# Camera_Gantry.net
KiCad netlist of a schematic drawn in EAGLE
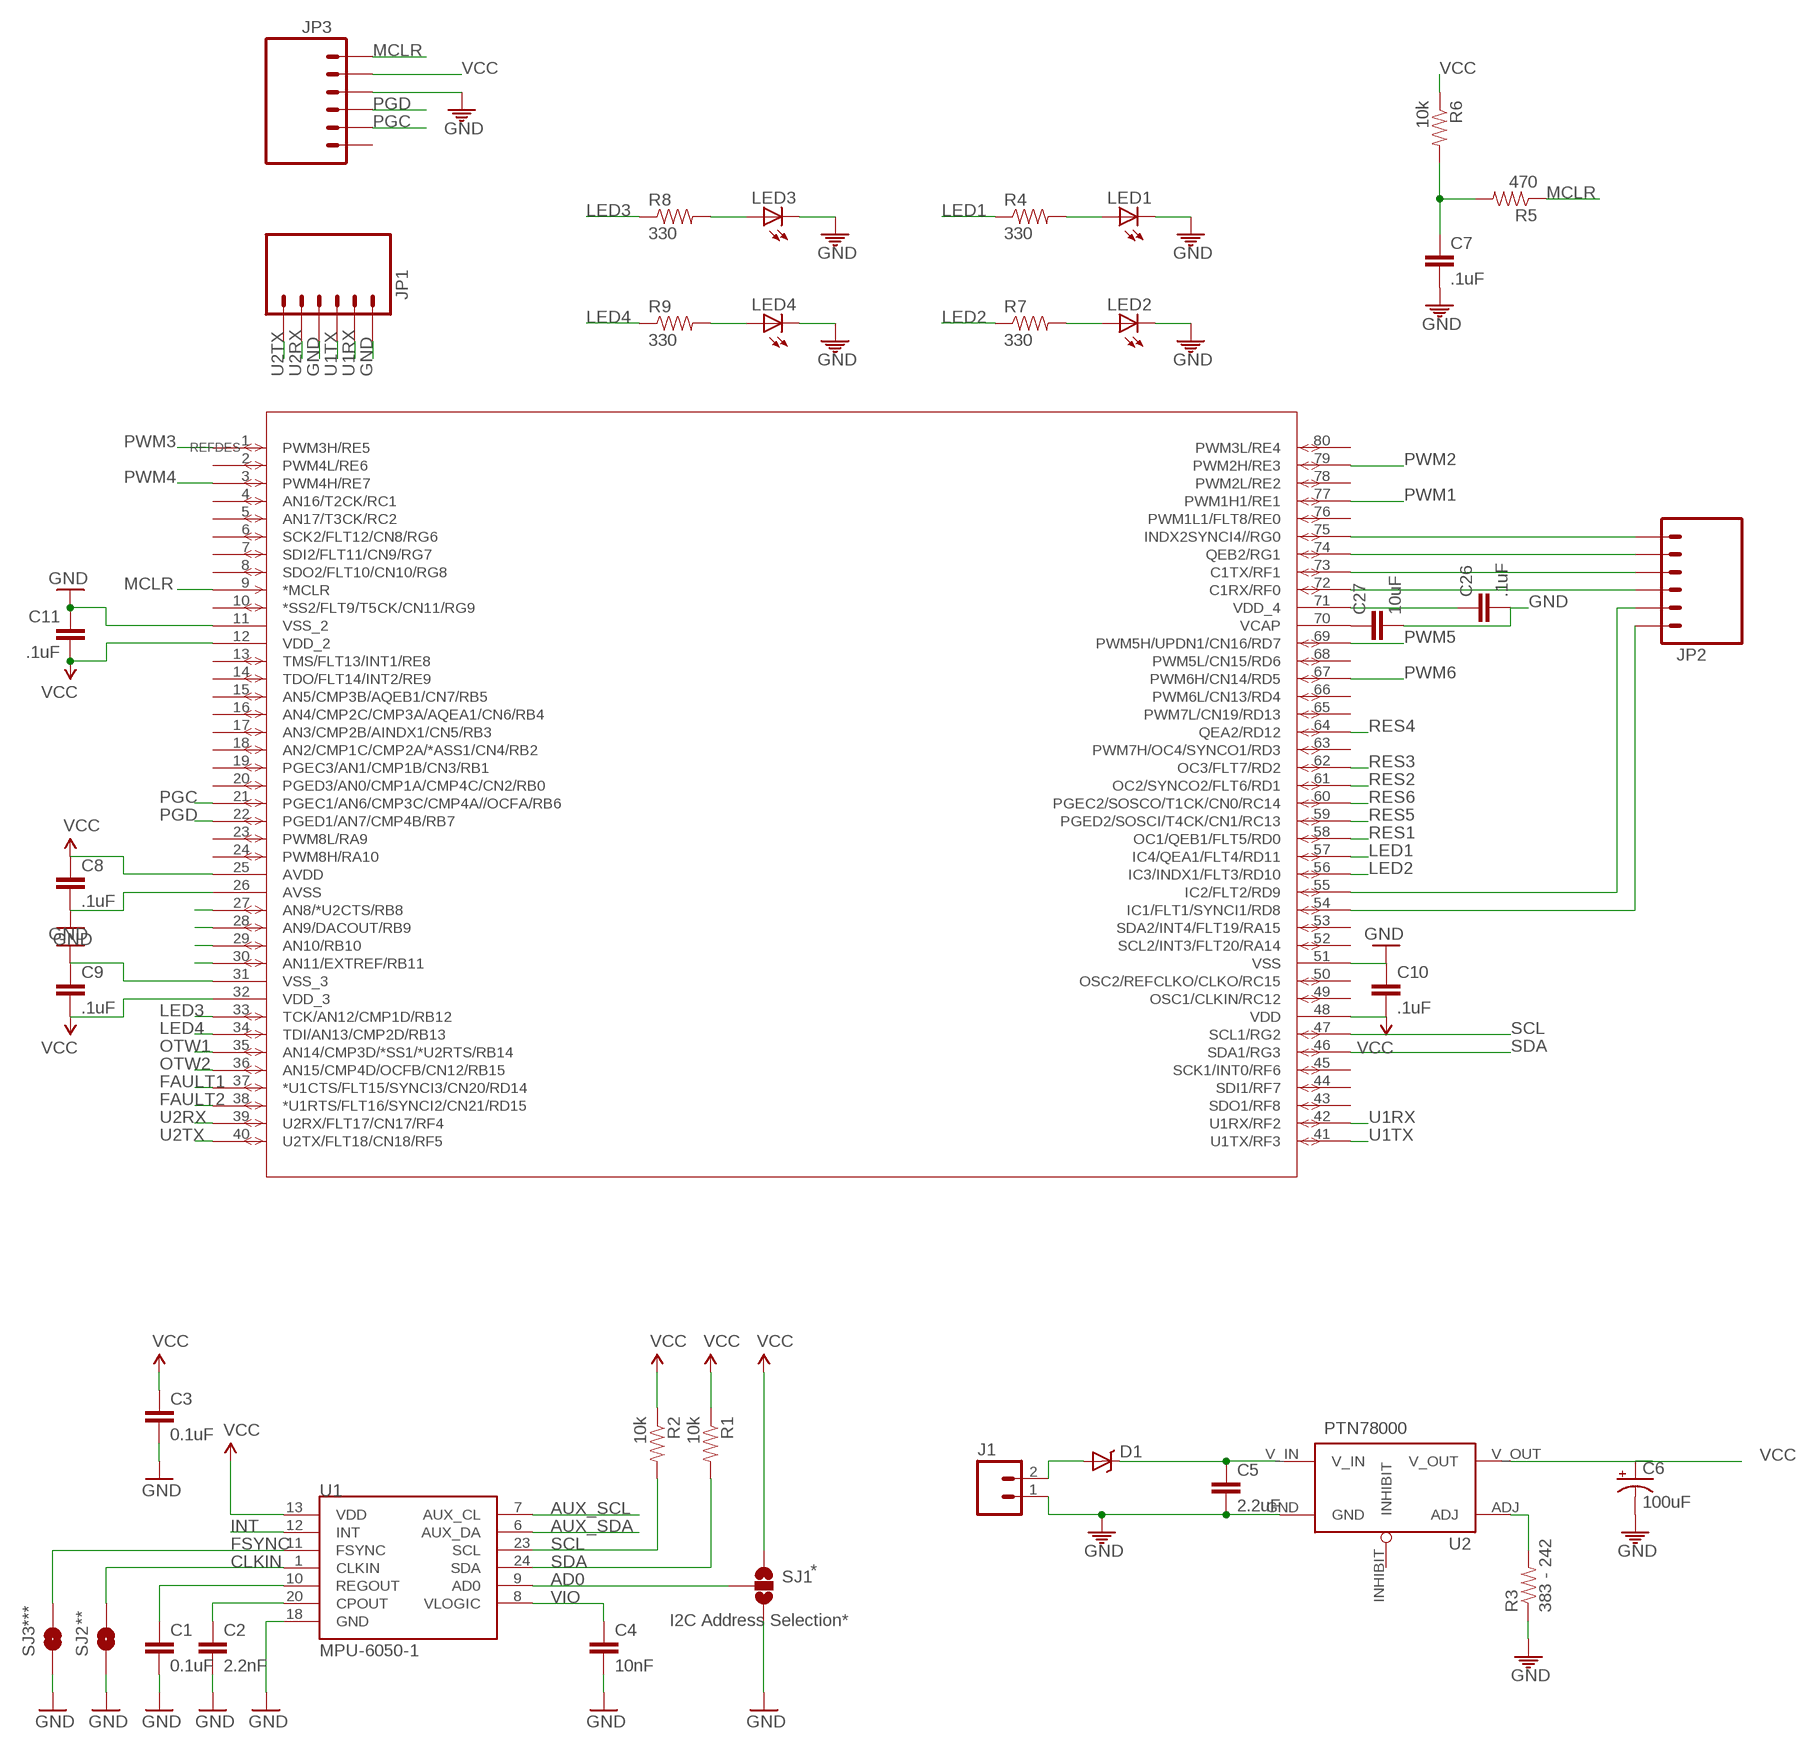
[diagram p0: schematic, sheet 1, part 1 of 2]
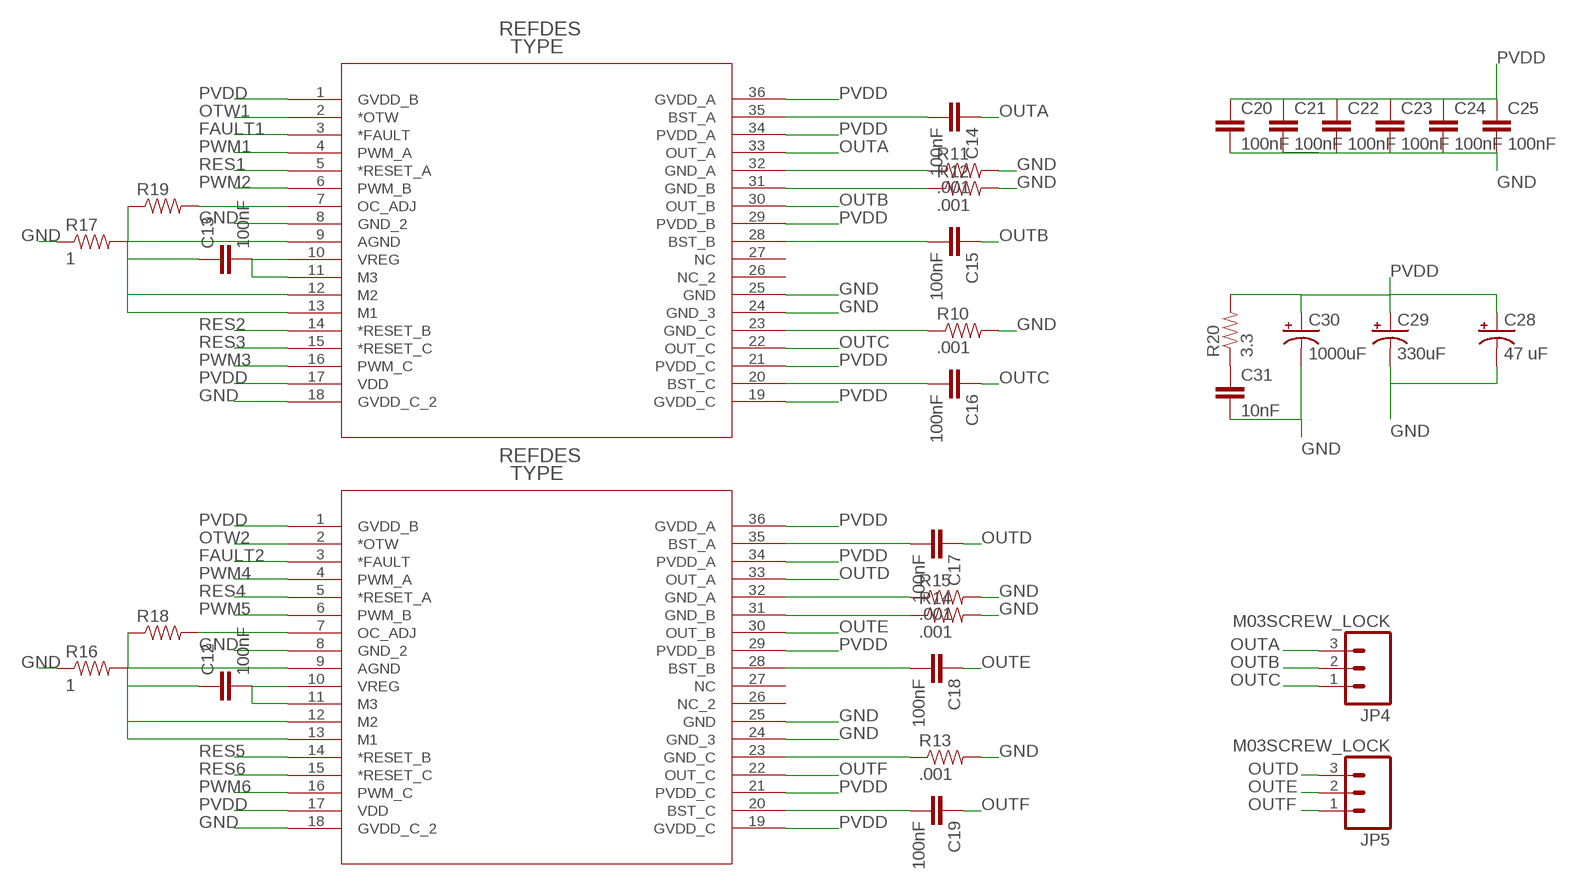
[diagram p1: schematic, sheet 1, part 2 of 2]

(export (version "E")
  (design (tool "Eeschema 10.0.6"))
  (components
    (comp (ref "C1")
      (value "0.1uF")
      (footprint "eagle-import:1206")
      (libsource (lib "eagle-import") (part "CAP1206"))
    )
    (comp (ref "C2")
      (value "2.2nF")
      (footprint "eagle-import:1206")
      (libsource (lib "eagle-import") (part "CAP1206"))
    )
    (comp (ref "C3")
      (value "0.1uF")
      (footprint "eagle-import:1206")
      (libsource (lib "eagle-import") (part "CAP1206"))
    )
    (comp (ref "C4")
      (value "10nF")
      (footprint "eagle-import:1206")
      (libsource (lib "eagle-import") (part "CAP1206"))
    )
    (comp (ref "C5")
      (value "2.2uF")
      (footprint "eagle-import:1206")
      (libsource (lib "eagle-import") (part "CMPE118lib_CAP1206"))
    )
    (comp (ref "C6")
      (value "100uF")
      (footprint "eagle-import:CPOL-RADIAL-100UF-25V")
      (libsource (lib "eagle-import") (part "CAP_POLPTH1"))
    )
    (comp (ref "C7")
      (value ".1uF")
      (footprint "eagle-import:1206")
      (libsource (lib "eagle-import") (part "CMPE118lib_CAP1206"))
    )
    (comp (ref "C8")
      (value ".1uF")
      (footprint "eagle-import:1206")
      (libsource (lib "eagle-import") (part "CAP1206"))
    )
    (comp (ref "C9")
      (value ".1uF")
      (footprint "eagle-import:1206")
      (libsource (lib "eagle-import") (part "CAP1206"))
    )
    (comp (ref "C10")
      (value ".1uF")
      (footprint "eagle-import:1206")
      (libsource (lib "eagle-import") (part "CAP1206"))
    )
    (comp (ref "C11")
      (value ".1uF")
      (footprint "eagle-import:1206")
      (libsource (lib "eagle-import") (part "CAP1206"))
    )
    (comp (ref "C12")
      (value "100nF")
      (footprint "eagle-import:1206")
      (libsource (lib "eagle-import") (part "CAP1206"))
    )
    (comp (ref "C13")
      (value "100nF")
      (footprint "eagle-import:1206")
      (libsource (lib "eagle-import") (part "CAP1206"))
    )
    (comp (ref "C14")
      (value "100nF")
      (footprint "eagle-import:1206")
      (libsource (lib "eagle-import") (part "CAP1206"))
    )
    (comp (ref "C15")
      (value "100nF")
      (footprint "eagle-import:1206")
      (libsource (lib "eagle-import") (part "CAP1206"))
    )
    (comp (ref "C16")
      (value "100nF")
      (footprint "eagle-import:1206")
      (libsource (lib "eagle-import") (part "CAP1206"))
    )
    (comp (ref "C17")
      (value "100nF")
      (footprint "eagle-import:1206")
      (libsource (lib "eagle-import") (part "CAP1206"))
    )
    (comp (ref "C18")
      (value "100nF")
      (footprint "eagle-import:1206")
      (libsource (lib "eagle-import") (part "CAP1206"))
    )
    (comp (ref "C19")
      (value "100nF")
      (footprint "eagle-import:1206")
      (libsource (lib "eagle-import") (part "CAP1206"))
    )
    (comp (ref "C20")
      (value "100nF")
      (footprint "eagle-import:1206")
      (libsource (lib "eagle-import") (part "CAP1206"))
    )
    (comp (ref "C21")
      (value "100nF")
      (footprint "eagle-import:1206")
      (libsource (lib "eagle-import") (part "CAP1206"))
    )
    (comp (ref "C22")
      (value "100nF")
      (footprint "eagle-import:1206")
      (libsource (lib "eagle-import") (part "CAP1206"))
    )
    (comp (ref "C23")
      (value "100nF")
      (footprint "eagle-import:1206")
      (libsource (lib "eagle-import") (part "CAP1206"))
    )
    (comp (ref "C24")
      (value "100nF")
      (footprint "eagle-import:1206")
      (libsource (lib "eagle-import") (part "CAP1206"))
    )
    (comp (ref "C25")
      (value "100nF")
      (footprint "eagle-import:1206")
      (libsource (lib "eagle-import") (part "CAP1206"))
    )
    (comp (ref "C26")
      (value ".1uF")
      (footprint "eagle-import:1206")
      (libsource (lib "eagle-import") (part "CAP1206"))
    )
    (comp (ref "C27")
      (value "10uF")
      (footprint "eagle-import:1206")
      (libsource (lib "eagle-import") (part "CAP1206"))
    )
    (comp (ref "C28")
      (value "47 uF")
      (footprint "eagle-import:CPOL-RADIAL-10UF-25V")
      (libsource (lib "eagle-import") (part "CAP_POLPTH2"))
    )
    (comp (ref "C29")
      (value "330uF")
      (footprint "eagle-import:CPOL-RADIAL-100UF-25V")
      (libsource (lib "eagle-import") (part "CAP_POLPTH1"))
    )
    (comp (ref "C30")
      (value "1000uF")
      (footprint "eagle-import:CPOL-RADIAL-1000UF-25V")
      (libsource (lib "eagle-import") (part "CAP_POLPTH4"))
    )
    (comp (ref "C31")
      (value "10nF")
      (footprint "eagle-import:1206")
      (libsource (lib "eagle-import") (part "CAP1206"))
    )
    (comp (ref "D1")
      (value "DIODE-SCHOTTKY240A")
      (footprint "eagle-import:SMA-DIODE-B240A")
      (libsource (lib "eagle-import") (part "DIODE-SCHOTTKY240A"))
    )
    (comp (ref "J1")
      (value "M025MM")
      (footprint "eagle-import:SCREWTERMINAL-5MM-2")
      (libsource (lib "eagle-import") (part "M025MM"))
    )
    (comp (ref "JP1")
      (value "M06SIP")
      (footprint "eagle-import:1X06")
      (libsource (lib "eagle-import") (part "M06SIP"))
    )
    (comp (ref "JP2")
      (value "M06SIP")
      (footprint "eagle-import:1X06")
      (libsource (lib "eagle-import") (part "M06SIP"))
    )
    (comp (ref "JP3")
      (value "M06LOCK")
      (footprint "eagle-import:1X06_LOCK")
      (libsource (lib "eagle-import") (part "CMPE118lib_M06LOCK"))
    )
    (comp (ref "JP4")
      (value "M03SCREW_LOCK")
      (footprint "eagle-import:SCREWTERMINAL-3.5MM-3_LOCK.007S")
      (libsource (lib "eagle-import") (part "M03SCREW_LOCK"))
    )
    (comp (ref "JP5")
      (value "M03SCREW_LOCK")
      (footprint "eagle-import:SCREWTERMINAL-3.5MM-3_LOCK.007S")
      (libsource (lib "eagle-import") (part "M03SCREW_LOCK"))
    )
    (comp (ref "LED1")
      (value "LED1206")
      (footprint "eagle-import:LED-1206")
      (fields (field (name "COLOR") "red"))
      (libsource (lib "eagle-import") (part "LED1206"))
    )
    (comp (ref "LED2")
      (value "LED1206")
      (footprint "eagle-import:LED-1206")
      (fields (field (name "COLOR") "red"))
      (libsource (lib "eagle-import") (part "LED1206"))
    )
    (comp (ref "LED3")
      (value "LED1206")
      (footprint "eagle-import:LED-1206")
      (fields (field (name "COLOR") "red"))
      (libsource (lib "eagle-import") (part "LED1206"))
    )
    (comp (ref "LED4")
      (value "LED1206")
      (footprint "eagle-import:LED-1206")
      (fields (field (name "COLOR") "red"))
      (libsource (lib "eagle-import") (part "LED1206"))
    )
    (comp (ref "R1")
      (value "10k")
      (footprint "eagle-import:0805")
      (libsource (lib "eagle-import") (part "CMPE118lib_RESISTOR0805-RES"))
    )
    (comp (ref "R2")
      (value "10k")
      (footprint "eagle-import:0805")
      (libsource (lib "eagle-import") (part "CMPE118lib_RESISTOR0805-RES"))
    )
    (comp (ref "R3")
      (value "383 - 242")
      (footprint "eagle-import:0805")
      (libsource (lib "eagle-import") (part "CMPE118lib_RESISTOR0805-RES"))
    )
    (comp (ref "R4")
      (value "330")
      (footprint "eagle-import:0805")
      (libsource (lib "eagle-import") (part "CMPE118lib_RESISTOR0805-RES"))
    )
    (comp (ref "R5")
      (value "470")
      (footprint "eagle-import:0805")
      (libsource (lib "eagle-import") (part "CMPE118lib_RESISTOR0805-RES"))
    )
    (comp (ref "R6")
      (value "10k")
      (footprint "eagle-import:0805")
      (libsource (lib "eagle-import") (part "CMPE118lib_RESISTOR0805-RES"))
    )
    (comp (ref "R7")
      (value "330")
      (footprint "eagle-import:0805")
      (libsource (lib "eagle-import") (part "CMPE118lib_RESISTOR0805-RES"))
    )
    (comp (ref "R8")
      (value "330")
      (footprint "eagle-import:0805")
      (libsource (lib "eagle-import") (part "CMPE118lib_RESISTOR0805-RES"))
    )
    (comp (ref "R9")
      (value "330")
      (footprint "eagle-import:0805")
      (libsource (lib "eagle-import") (part "CMPE118lib_RESISTOR0805-RES"))
    )
    (comp (ref "R10")
      (value ".001")
      (footprint "eagle-import:R2512")
      (libsource (lib "eagle-import") (part "RESISTOR2512"))
    )
    (comp (ref "R11")
      (value ".001")
      (footprint "eagle-import:R2512")
      (libsource (lib "eagle-import") (part "RESISTOR2512"))
    )
    (comp (ref "R12")
      (value ".001")
      (footprint "eagle-import:R2512")
      (libsource (lib "eagle-import") (part "RESISTOR2512"))
    )
    (comp (ref "R13")
      (value ".001")
      (footprint "eagle-import:R2512")
      (libsource (lib "eagle-import") (part "RESISTOR2512"))
    )
    (comp (ref "R14")
      (value ".001")
      (footprint "eagle-import:R2512")
      (libsource (lib "eagle-import") (part "RESISTOR2512"))
    )
    (comp (ref "R15")
      (value ".001")
      (footprint "eagle-import:R2512")
      (libsource (lib "eagle-import") (part "RESISTOR2512"))
    )
    (comp (ref "R16")
      (value "1")
      (footprint "eagle-import:0805")
      (libsource (lib "eagle-import") (part "RESISTOR0805-RES"))
    )
    (comp (ref "R17")
      (value "1")
      (footprint "eagle-import:0805")
      (libsource (lib "eagle-import") (part "RESISTOR0805-RES"))
    )
    (comp (ref "R18")
      (value "RESISTOR0805-RES")
      (footprint "eagle-import:0805")
      (libsource (lib "eagle-import") (part "RESISTOR0805-RES"))
    )
    (comp (ref "R19")
      (value "RESISTOR0805-RES")
      (footprint "eagle-import:0805")
      (libsource (lib "eagle-import") (part "RESISTOR0805-RES"))
    )
    (comp (ref "R20")
      (value "3.3")
      (footprint "eagle-import:0805")
      (libsource (lib "eagle-import") (part "RESISTOR0805-RES"))
    )
    (comp (ref "SJ1")
      (value "SOLDERJUMPER_2WAYPASTE2&3")
      (footprint "eagle-import:SJ_3_PASTE2&3")
      (libsource (lib "eagle-import") (part "SOLDERJUMPER_2WAYPASTE2&3"))
    )
    (comp (ref "SJ2")
      (value "SOLDERJUMPERTRACE")
      (footprint "eagle-import:SJ_2S-TRACE")
      (libsource (lib "eagle-import") (part "SOLDERJUMPERTRACE"))
    )
    (comp (ref "SJ3")
      (value "SOLDERJUMPERTRACE")
      (footprint "eagle-import:SJ_2S-TRACE")
      (libsource (lib "eagle-import") (part "SOLDERJUMPERTRACE"))
    )
    (comp (ref "U$1")
      (value "DSPIC33FJ64GS608")
      (footprint "eagle-import:TQFP80_12X12MC")
      (libsource (lib "eagle-import") (part "DSPIC33FJ64GS608"))
    )
    (comp (ref "U1")
      (value "MPU-6050-1")
      (footprint "eagle-import:QFN-24-4MM2")
      (libsource (lib "eagle-import") (part "MPU-6050-1"))
    )
    (comp (ref "U2")
      (value "PTN78000")
      (footprint "eagle-import:PTN78000")
      (libsource (lib "eagle-import") (part "PTN78000THROUGH-HOLE"))
    )
    (comp (ref "U3")
      (value "DRV8332_DKD_36")
      (footprint "eagle-import:DKD36")
      (libsource (lib "eagle-import") (part "DRV8332_DKD_36"))
    )
    (comp (ref "U4")
      (value "DRV8332_DKD_36")
      (footprint "eagle-import:DKD36")
      (libsource (lib "eagle-import") (part "DRV8332_DKD_36"))
    )
  )
  (nets
    (net (code "1") (name "/AD0") (class "Default")
      (node (ref "SJ1") (pin "2") (pinfunction "2_2") (pintype "passive"))
      (node (ref "U1") (pin "9") (pinfunction "AD0_9") (pintype "bidirectional"))
    )
    (net (code "2") (name "/AUX_SCL") (class "Default")
      (node (ref "U1") (pin "7") (pinfunction "AUX_CL_7") (pintype "bidirectional"))
    )
    (net (code "3") (name "/AUX_SDA") (class "Default")
      (node (ref "U1") (pin "6") (pinfunction "AUX_DA_6") (pintype "bidirectional"))
    )
    (net (code "4") (name "/CLKIN") (class "Default")
      (node (ref "SJ2") (pin "2") (pinfunction "2_2") (pintype "passive"))
      (node (ref "U1") (pin "1") (pinfunction "CLKIN_1") (pintype "bidirectional"))
    )
    (net (code "5") (name "/FAULT1") (class "Default")
      (node (ref "U$1") (pin "37") (pinfunction "*U1CTS/FLT15/SYNCI3/CN20/RD14_37") (pintype "passive"))
      (node (ref "U3") (pin "3") (pinfunction "*FAULT_3") (pintype "passive"))
    )
    (net (code "6") (name "/FAULT2") (class "Default")
      (node (ref "U$1") (pin "38") (pinfunction "*U1RTS/FLT16/SYNCI2/CN21/RD15_38") (pintype "passive"))
      (node (ref "U4") (pin "3") (pinfunction "*FAULT_3") (pintype "passive"))
    )
    (net (code "7") (name "/FSYNC") (class "Default")
      (node (ref "SJ3") (pin "2") (pinfunction "2_2") (pintype "passive"))
      (node (ref "U1") (pin "11") (pinfunction "FSYNC_11") (pintype "bidirectional"))
    )
    (net (code "8") (name "/INT") (class "Default")
      (node (ref "U1") (pin "12") (pinfunction "INT_12") (pintype "bidirectional"))
    )
    (net (code "9") (name "/LED1") (class "Default")
      (node (ref "R4") (pin "1") (pinfunction "1_1") (pintype "passive"))
      (node (ref "U$1") (pin "57") (pinfunction "IC4/QEA1/FLT4/RD11_57") (pintype "passive"))
    )
    (net (code "10") (name "/LED2") (class "Default")
      (node (ref "R7") (pin "1") (pinfunction "1_1") (pintype "passive"))
      (node (ref "U$1") (pin "56") (pinfunction "IC3/INDX1/FLT3/RD10_56") (pintype "passive"))
    )
    (net (code "11") (name "/LED3") (class "Default")
      (node (ref "R8") (pin "1") (pinfunction "1_1") (pintype "passive"))
      (node (ref "U$1") (pin "33") (pinfunction "TCK/AN12/CMP1D/RB12_33") (pintype "passive"))
    )
    (net (code "12") (name "/LED4") (class "Default")
      (node (ref "R9") (pin "1") (pinfunction "1_1") (pintype "passive"))
      (node (ref "U$1") (pin "34") (pinfunction "TDI/AN13/CMP2D/RB13_34") (pintype "passive"))
    )
    (net (code "13") (name "/MCLR") (class "Default")
      (node (ref "JP3") (pin "1") (pinfunction "1_1") (pintype "passive"))
      (node (ref "R5") (pin "1") (pinfunction "1_1") (pintype "passive"))
      (node (ref "U$1") (pin "9") (pinfunction "*MCLR_9") (pintype "passive"))
    )
    (net (code "14") (name "/OTW1") (class "Default")
      (node (ref "U$1") (pin "35") (pinfunction "AN14/CMP3D/*SS1/*U2RTS/RB14_35") (pintype "passive"))
      (node (ref "U3") (pin "2") (pinfunction "*OTW_2") (pintype "passive"))
    )
    (net (code "15") (name "/OTW2") (class "Default")
      (node (ref "U$1") (pin "36") (pinfunction "AN15/CMP4D/OCFB/CN12/RB15_36") (pintype "passive"))
      (node (ref "U4") (pin "2") (pinfunction "*OTW_2") (pintype "passive"))
    )
    (net (code "16") (name "/OUTA") (class "Default")
      (node (ref "C14") (pin "1") (pinfunction "1_1") (pintype "passive"))
      (node (ref "JP4") (pin "3") (pinfunction "3_3") (pintype "passive"))
      (node (ref "U3") (pin "33") (pinfunction "OUT_A_33") (pintype "passive"))
    )
    (net (code "17") (name "/OUTB") (class "Default")
      (node (ref "C15") (pin "1") (pinfunction "1_1") (pintype "passive"))
      (node (ref "JP4") (pin "2") (pinfunction "2_2") (pintype "passive"))
      (node (ref "U3") (pin "30") (pinfunction "OUT_B_30") (pintype "passive"))
    )
    (net (code "18") (name "/OUTC") (class "Default")
      (node (ref "C16") (pin "1") (pinfunction "1_1") (pintype "passive"))
      (node (ref "JP4") (pin "1") (pinfunction "1_1") (pintype "passive"))
      (node (ref "U3") (pin "22") (pinfunction "OUT_C_22") (pintype "passive"))
    )
    (net (code "19") (name "/OUTD") (class "Default")
      (node (ref "C17") (pin "1") (pinfunction "1_1") (pintype "passive"))
      (node (ref "JP5") (pin "3") (pinfunction "3_3") (pintype "passive"))
      (node (ref "U4") (pin "33") (pinfunction "OUT_A_33") (pintype "passive"))
    )
    (net (code "20") (name "/OUTE") (class "Default")
      (node (ref "C18") (pin "1") (pinfunction "1_1") (pintype "passive"))
      (node (ref "JP5") (pin "2") (pinfunction "2_2") (pintype "passive"))
      (node (ref "U4") (pin "30") (pinfunction "OUT_B_30") (pintype "passive"))
    )
    (net (code "21") (name "/OUTF") (class "Default")
      (node (ref "C19") (pin "1") (pinfunction "1_1") (pintype "passive"))
      (node (ref "JP5") (pin "1") (pinfunction "1_1") (pintype "passive"))
      (node (ref "U4") (pin "22") (pinfunction "OUT_C_22") (pintype "passive"))
    )
    (net (code "22") (name "/PGC") (class "Default")
      (node (ref "JP3") (pin "5") (pinfunction "5_5") (pintype "passive"))
      (node (ref "U$1") (pin "21") (pinfunction "PGEC1/AN6/CMP3C/CMP4A//OCFA/RB6_21") (pintype "passive"))
    )
    (net (code "23") (name "/PGD") (class "Default")
      (node (ref "JP3") (pin "4") (pinfunction "4_4") (pintype "passive"))
      (node (ref "U$1") (pin "22") (pinfunction "PGED1/AN7/CMP4B/RB7_22") (pintype "passive"))
    )
    (net (code "24") (name "/PVDD") (class "Default")
      (node (ref "C20") (pin "1") (pinfunction "1_1") (pintype "passive"))
      (node (ref "C21") (pin "1") (pinfunction "1_1") (pintype "passive"))
      (node (ref "C22") (pin "1") (pinfunction "1_1") (pintype "passive"))
      (node (ref "C23") (pin "1") (pinfunction "1_1") (pintype "passive"))
      (node (ref "C24") (pin "1") (pinfunction "1_1") (pintype "passive"))
      (node (ref "C25") (pin "1") (pinfunction "1_1") (pintype "passive"))
      (node (ref "C28") (pin "1") (pinfunction "+_1") (pintype "passive"))
      (node (ref "C29") (pin "1") (pinfunction "+_1") (pintype "passive"))
      (node (ref "C30") (pin "1") (pinfunction "+_1") (pintype "passive"))
      (node (ref "C5") (pin "1") (pinfunction "1_1") (pintype "passive"))
      (node (ref "D1") (pin "C") (pinfunction "C_C") (pintype "passive"))
      (node (ref "R20") (pin "2") (pinfunction "2_2") (pintype "passive"))
      (node (ref "U2") (pin "V_IN") (pinfunction "V_IN_V_IN") (pintype "power_in"))
      (node (ref "U3") (pin "1") (pinfunction "GVDD_B_1") (pintype "passive"))
      (node (ref "U3") (pin "17") (pinfunction "VDD_17") (pintype "passive"))
      (node (ref "U3") (pin "19") (pinfunction "GVDD_C_19") (pintype "passive"))
      (node (ref "U3") (pin "21") (pinfunction "PVDD_C_21") (pintype "passive"))
      (node (ref "U3") (pin "29") (pinfunction "PVDD_B_29") (pintype "passive"))
      (node (ref "U3") (pin "34") (pinfunction "PVDD_A_34") (pintype "passive"))
      (node (ref "U3") (pin "36") (pinfunction "GVDD_A_36") (pintype "passive"))
      (node (ref "U4") (pin "1") (pinfunction "GVDD_B_1") (pintype "passive"))
      (node (ref "U4") (pin "17") (pinfunction "VDD_17") (pintype "passive"))
      (node (ref "U4") (pin "19") (pinfunction "GVDD_C_19") (pintype "passive"))
      (node (ref "U4") (pin "21") (pinfunction "PVDD_C_21") (pintype "passive"))
      (node (ref "U4") (pin "29") (pinfunction "PVDD_B_29") (pintype "passive"))
      (node (ref "U4") (pin "34") (pinfunction "PVDD_A_34") (pintype "passive"))
      (node (ref "U4") (pin "36") (pinfunction "GVDD_A_36") (pintype "passive"))
    )
    (net (code "25") (name "/PWM1") (class "Default")
      (node (ref "U$1") (pin "77") (pinfunction "PWM1H1/RE1_77") (pintype "passive"))
      (node (ref "U3") (pin "4") (pinfunction "PWM_A_4") (pintype "passive"))
    )
    (net (code "26") (name "/PWM2") (class "Default")
      (node (ref "U$1") (pin "79") (pinfunction "PWM2H/RE3_79") (pintype "passive"))
      (node (ref "U3") (pin "6") (pinfunction "PWM_B_6") (pintype "passive"))
    )
    (net (code "27") (name "/PWM3") (class "Default")
      (node (ref "U$1") (pin "1") (pinfunction "PWM3H/RE5_1") (pintype "passive"))
      (node (ref "U3") (pin "16") (pinfunction "PWM_C_16") (pintype "passive"))
    )
    (net (code "28") (name "/PWM4") (class "Default")
      (node (ref "U$1") (pin "3") (pinfunction "PWM4H/RE7_3") (pintype "passive"))
      (node (ref "U4") (pin "4") (pinfunction "PWM_A_4") (pintype "passive"))
    )
    (net (code "29") (name "/PWM5") (class "Default")
      (node (ref "U$1") (pin "69") (pinfunction "PWM5H/UPDN1/CN16/RD7_69") (pintype "passive"))
      (node (ref "U4") (pin "6") (pinfunction "PWM_B_6") (pintype "passive"))
    )
    (net (code "30") (name "/PWM6") (class "Default")
      (node (ref "U$1") (pin "67") (pinfunction "PWM6H/CN14/RD5_67") (pintype "passive"))
      (node (ref "U4") (pin "16") (pinfunction "PWM_C_16") (pintype "passive"))
    )
    (net (code "31") (name "/RES1") (class "Default")
      (node (ref "U$1") (pin "58") (pinfunction "OC1/QEB1/FLT5/RD0_58") (pintype "passive"))
      (node (ref "U3") (pin "5") (pinfunction "*RESET_A_5") (pintype "passive"))
    )
    (net (code "32") (name "/RES2") (class "Default")
      (node (ref "U$1") (pin "61") (pinfunction "OC2/SYNCO2/FLT6/RD1_61") (pintype "passive"))
      (node (ref "U3") (pin "14") (pinfunction "*RESET_B_14") (pintype "passive"))
    )
    (net (code "33") (name "/RES3") (class "Default")
      (node (ref "U$1") (pin "62") (pinfunction "OC3/FLT7/RD2_62") (pintype "passive"))
      (node (ref "U3") (pin "15") (pinfunction "*RESET_C_15") (pintype "passive"))
    )
    (net (code "34") (name "/RES4") (class "Default")
      (node (ref "U$1") (pin "64") (pinfunction "QEA2/RD12_64") (pintype "passive"))
      (node (ref "U4") (pin "5") (pinfunction "*RESET_A_5") (pintype "passive"))
    )
    (net (code "35") (name "/RES5") (class "Default")
      (node (ref "U$1") (pin "59") (pinfunction "PGED2/SOSCI/T4CK/CN1/RC13_59") (pintype "passive"))
      (node (ref "U4") (pin "14") (pinfunction "*RESET_B_14") (pintype "passive"))
    )
    (net (code "36") (name "/RES6") (class "Default")
      (node (ref "U$1") (pin "60") (pinfunction "PGEC2/SOSCO/T1CK/CN0/RC14_60") (pintype "passive"))
      (node (ref "U4") (pin "15") (pinfunction "*RESET_C_15") (pintype "passive"))
    )
    (net (code "37") (name "/SCL") (class "Default")
      (node (ref "R2") (pin "2") (pinfunction "2_2") (pintype "passive"))
      (node (ref "U$1") (pin "47") (pinfunction "SCL1/RG2_47") (pintype "passive"))
      (node (ref "U1") (pin "23") (pinfunction "SCL_23") (pintype "bidirectional"))
    )
    (net (code "38") (name "/SDA") (class "Default")
      (node (ref "R1") (pin "2") (pinfunction "2_2") (pintype "passive"))
      (node (ref "U$1") (pin "46") (pinfunction "SDA1/RG3_46") (pintype "passive"))
      (node (ref "U1") (pin "24") (pinfunction "SDA_24") (pintype "bidirectional"))
    )
    (net (code "39") (name "/U1RX") (class "Default")
      (node (ref "JP1") (pin "2") (pinfunction "2_2") (pintype "passive"))
      (node (ref "U$1") (pin "42") (pinfunction "U1RX/RF2_42") (pintype "passive"))
    )
    (net (code "40") (name "/U1TX") (class "Default")
      (node (ref "JP1") (pin "3") (pinfunction "3_3") (pintype "passive"))
      (node (ref "U$1") (pin "41") (pinfunction "U1TX/RF3_41") (pintype "passive"))
    )
    (net (code "41") (name "/U2RX") (class "Default")
      (node (ref "JP1") (pin "5") (pinfunction "5_5") (pintype "passive"))
      (node (ref "U$1") (pin "39") (pinfunction "U2RX/FLT17/CN17/RF4_39") (pintype "passive"))
    )
    (net (code "42") (name "/U2TX") (class "Default")
      (node (ref "JP1") (pin "6") (pinfunction "6_6") (pintype "passive"))
      (node (ref "U$1") (pin "40") (pinfunction "U2TX/FLT18/CN18/RF5_40") (pintype "passive"))
    )
    (net (code "43") (name "/VIO") (class "Default")
      (node (ref "C4") (pin "1") (pinfunction "1_1") (pintype "passive"))
      (node (ref "U1") (pin "8") (pinfunction "VLOGIC_8") (pintype "bidirectional"))
    )
    (net (code "44") (name "GND") (class "Default")
      (node (ref "C1") (pin "2") (pinfunction "2_2") (pintype "passive"))
      (node (ref "C10") (pin "1") (pinfunction "1_1") (pintype "passive"))
      (node (ref "C11") (pin "1") (pinfunction "1_1") (pintype "passive"))
      (node (ref "C2") (pin "2") (pinfunction "2_2") (pintype "passive"))
      (node (ref "C20") (pin "2") (pinfunction "2_2") (pintype "passive"))
      (node (ref "C21") (pin "2") (pinfunction "2_2") (pintype "passive"))
      (node (ref "C22") (pin "2") (pinfunction "2_2") (pintype "passive"))
      (node (ref "C23") (pin "2") (pinfunction "2_2") (pintype "passive"))
      (node (ref "C24") (pin "2") (pinfunction "2_2") (pintype "passive"))
      (node (ref "C25") (pin "2") (pinfunction "2_2") (pintype "passive"))
      (node (ref "C26") (pin "2") (pinfunction "2_2") (pintype "passive"))
      (node (ref "C27") (pin "2") (pinfunction "2_2") (pintype "passive"))
      (node (ref "C28") (pin "2") (pinfunction "-_2") (pintype "passive"))
      (node (ref "C29") (pin "2") (pinfunction "-_2") (pintype "passive"))
      (node (ref "C3") (pin "2") (pinfunction "2_2") (pintype "passive"))
      (node (ref "C30") (pin "2") (pinfunction "-_2") (pintype "passive"))
      (node (ref "C31") (pin "2") (pinfunction "2_2") (pintype "passive"))
      (node (ref "C4") (pin "2") (pinfunction "2_2") (pintype "passive"))
      (node (ref "C5") (pin "2") (pinfunction "2_2") (pintype "passive"))
      (node (ref "C6") (pin "2") (pinfunction "-_2") (pintype "passive"))
      (node (ref "C7") (pin "2") (pinfunction "2_2") (pintype "passive"))
      (node (ref "C8") (pin "2") (pinfunction "2_2") (pintype "passive"))
      (node (ref "C9") (pin "1") (pinfunction "1_1") (pintype "passive"))
      (node (ref "J1") (pin "1") (pinfunction "1_1") (pintype "passive"))
      (node (ref "JP1") (pin "1") (pinfunction "1_1") (pintype "passive"))
      (node (ref "JP1") (pin "4") (pinfunction "4_4") (pintype "passive"))
      (node (ref "JP3") (pin "3") (pinfunction "3_3") (pintype "passive"))
      (node (ref "LED1") (pin "C") (pinfunction "C_C") (pintype "passive"))
      (node (ref "LED2") (pin "C") (pinfunction "C_C") (pintype "passive"))
      (node (ref "LED3") (pin "C") (pinfunction "C_C") (pintype "passive"))
      (node (ref "LED4") (pin "C") (pinfunction "C_C") (pintype "passive"))
      (node (ref "R10") (pin "2") (pinfunction "2_2") (pintype "passive"))
      (node (ref "R11") (pin "2") (pinfunction "2_2") (pintype "passive"))
      (node (ref "R12") (pin "2") (pinfunction "2_2") (pintype "passive"))
      (node (ref "R13") (pin "2") (pinfunction "2_2") (pintype "passive"))
      (node (ref "R14") (pin "2") (pinfunction "2_2") (pintype "passive"))
      (node (ref "R15") (pin "2") (pinfunction "2_2") (pintype "passive"))
      (node (ref "R16") (pin "1") (pinfunction "1_1") (pintype "passive"))
      (node (ref "R17") (pin "1") (pinfunction "1_1") (pintype "passive"))
      (node (ref "R3") (pin "1") (pinfunction "1_1") (pintype "passive"))
      (node (ref "SJ1") (pin "3") (pinfunction "3_3") (pintype "passive"))
      (node (ref "SJ2") (pin "1") (pinfunction "1_1") (pintype "passive"))
      (node (ref "SJ3") (pin "1") (pinfunction "1_1") (pintype "passive"))
      (node (ref "U$1") (pin "11") (pinfunction "VSS_2_11") (pintype "passive"))
      (node (ref "U$1") (pin "26") (pinfunction "AVSS_26") (pintype "passive"))
      (node (ref "U$1") (pin "31") (pinfunction "VSS_3_31") (pintype "passive"))
      (node (ref "U$1") (pin "51") (pinfunction "VSS_51") (pintype "passive"))
      (node (ref "U1") (pin "18") (pinfunction "GND_18") (pintype "bidirectional"))
      (node (ref "U2") (pin "GND") (pinfunction "GND_GND") (pintype "power_in"))
      (node (ref "U3") (pin "18") (pinfunction "GVDD_C_2_18") (pintype "passive"))
      (node (ref "U3") (pin "24") (pinfunction "GND_3_24") (pintype "passive"))
      (node (ref "U3") (pin "25") (pinfunction "GND_25") (pintype "passive"))
      (node (ref "U3") (pin "8") (pinfunction "GND_2_8") (pintype "passive"))
      (node (ref "U4") (pin "18") (pinfunction "GVDD_C_2_18") (pintype "passive"))
      (node (ref "U4") (pin "24") (pinfunction "GND_3_24") (pintype "passive"))
      (node (ref "U4") (pin "25") (pinfunction "GND_25") (pintype "passive"))
      (node (ref "U4") (pin "8") (pinfunction "GND_2_8") (pintype "passive"))
    )
    (net (code "45") (name "Net-(C7-Pad1)") (class "Default")
      (node (ref "C7") (pin "1") (pinfunction "1_1") (pintype "passive"))
      (node (ref "R5") (pin "2") (pinfunction "2_2") (pintype "passive"))
      (node (ref "R6") (pin "2") (pinfunction "2_2") (pintype "passive"))
    )
    (net (code "46") (name "Net-(C31-Pad1)") (class "Default")
      (node (ref "C31") (pin "1") (pinfunction "1_1") (pintype "passive"))
      (node (ref "R20") (pin "1") (pinfunction "1_1") (pintype "passive"))
    )
    (net (code "47") (name "Net-(D1-PadA)") (class "Default")
      (node (ref "D1") (pin "A") (pinfunction "A_A") (pintype "passive"))
      (node (ref "J1") (pin "2") (pinfunction "2_2") (pintype "passive"))
    )
    (net (code "48") (name "Net-(LED1-PadA)") (class "Default")
      (node (ref "LED1") (pin "A") (pinfunction "A_A") (pintype "passive"))
      (node (ref "R4") (pin "2") (pinfunction "2_2") (pintype "passive"))
    )
    (net (code "49") (name "Net-(LED2-PadA)") (class "Default")
      (node (ref "LED2") (pin "A") (pinfunction "A_A") (pintype "passive"))
      (node (ref "R7") (pin "2") (pinfunction "2_2") (pintype "passive"))
    )
    (net (code "50") (name "Net-(LED3-PadA)") (class "Default")
      (node (ref "LED3") (pin "A") (pinfunction "A_A") (pintype "passive"))
      (node (ref "R8") (pin "2") (pinfunction "2_2") (pintype "passive"))
    )
    (net (code "51") (name "Net-(LED4-PadA)") (class "Default")
      (node (ref "LED4") (pin "A") (pinfunction "A_A") (pintype "passive"))
      (node (ref "R9") (pin "2") (pinfunction "2_2") (pintype "passive"))
    )
    (net (code "52") (name "Net-(R3-Pad2)") (class "Default")
      (node (ref "R3") (pin "2") (pinfunction "2_2") (pintype "passive"))
      (node (ref "U2") (pin "ADJ") (pinfunction "ADJ_ADJ") (pintype "input"))
    )
    (net (code "53") (name "Net-(U$1-C1RX{slash}RF0)") (class "Default")
      (node (ref "JP2") (pin "3") (pinfunction "3_3") (pintype "passive"))
      (node (ref "U$1") (pin "72") (pinfunction "C1RX/RF0_72") (pintype "passive"))
    )
    (net (code "54") (name "Net-(U$1-C1TX{slash}RF1)") (class "Default")
      (node (ref "JP2") (pin "4") (pinfunction "4_4") (pintype "passive"))
      (node (ref "U$1") (pin "73") (pinfunction "C1TX/RF1_73") (pintype "passive"))
    )
    (net (code "55") (name "Net-(U$1-IC1{slash}FLT1{slash}SYNCI1{slash}RD8)") (class "Default")
      (node (ref "JP2") (pin "1") (pinfunction "1_1") (pintype "passive"))
      (node (ref "U$1") (pin "54") (pinfunction "IC1/FLT1/SYNCI1/RD8_54") (pintype "passive"))
    )
    (net (code "56") (name "Net-(U$1-IC2{slash}FLT2{slash}RD9)") (class "Default")
      (node (ref "JP2") (pin "2") (pinfunction "2_2") (pintype "passive"))
      (node (ref "U$1") (pin "55") (pinfunction "IC2/FLT2/RD9_55") (pintype "passive"))
    )
    (net (code "57") (name "Net-(U$1-INDX2SYNCI4{slash}{slash}RG0)") (class "Default")
      (node (ref "JP2") (pin "6") (pinfunction "6_6") (pintype "passive"))
      (node (ref "U$1") (pin "75") (pinfunction "INDX2SYNCI4//RG0_75") (pintype "passive"))
    )
    (net (code "58") (name "Net-(U$1-QEB2{slash}RG1)") (class "Default")
      (node (ref "JP2") (pin "5") (pinfunction "5_5") (pintype "passive"))
      (node (ref "U$1") (pin "74") (pinfunction "QEB2/RG1_74") (pintype "passive"))
    )
    (net (code "59") (name "Net-(U$1-VCAP)") (class "Default")
      (node (ref "C27") (pin "1") (pinfunction "1_1") (pintype "passive"))
      (node (ref "U$1") (pin "70") (pinfunction "VCAP_70") (pintype "passive"))
    )
    (net (code "60") (name "Net-(U$1-VDD_4)") (class "Default")
      (node (ref "C26") (pin "1") (pinfunction "1_1") (pintype "passive"))
      (node (ref "U$1") (pin "71") (pinfunction "VDD_4_71") (pintype "passive"))
    )
    (net (code "61") (name "Net-(U1-CPOUT)") (class "Default")
      (node (ref "C2") (pin "1") (pinfunction "1_1") (pintype "passive"))
      (node (ref "U1") (pin "20") (pinfunction "CPOUT_20") (pintype "bidirectional"))
    )
    (net (code "62") (name "Net-(U1-REGOUT)") (class "Default")
      (node (ref "C1") (pin "1") (pinfunction "1_1") (pintype "passive"))
      (node (ref "U1") (pin "10") (pinfunction "REGOUT_10") (pintype "bidirectional"))
    )
    (net (code "63") (name "Net-(U3-AGND)") (class "Default")
      (node (ref "C13") (pin "1") (pinfunction "1_1") (pintype "passive"))
      (node (ref "R17") (pin "2") (pinfunction "2_2") (pintype "passive"))
      (node (ref "R19") (pin "1") (pinfunction "1_1") (pintype "passive"))
      (node (ref "U3") (pin "12") (pinfunction "M2_12") (pintype "passive"))
      (node (ref "U3") (pin "13") (pinfunction "M1_13") (pintype "passive"))
      (node (ref "U3") (pin "9") (pinfunction "AGND_9") (pintype "passive"))
    )
    (net (code "64") (name "Net-(U3-BST_A)") (class "Default")
      (node (ref "C14") (pin "2") (pinfunction "2_2") (pintype "passive"))
      (node (ref "U3") (pin "35") (pinfunction "BST_A_35") (pintype "passive"))
    )
    (net (code "65") (name "Net-(U3-BST_B)") (class "Default")
      (node (ref "C15") (pin "2") (pinfunction "2_2") (pintype "passive"))
      (node (ref "U3") (pin "28") (pinfunction "BST_B_28") (pintype "passive"))
    )
    (net (code "66") (name "Net-(U3-BST_C)") (class "Default")
      (node (ref "C16") (pin "2") (pinfunction "2_2") (pintype "passive"))
      (node (ref "U3") (pin "20") (pinfunction "BST_C_20") (pintype "passive"))
    )
    (net (code "67") (name "Net-(U3-GND_A)") (class "Default")
      (node (ref "R11") (pin "1") (pinfunction "1_1") (pintype "passive"))
      (node (ref "U3") (pin "32") (pinfunction "GND_A_32") (pintype "passive"))
    )
    (net (code "68") (name "Net-(U3-GND_B)") (class "Default")
      (node (ref "R12") (pin "1") (pinfunction "1_1") (pintype "passive"))
      (node (ref "U3") (pin "31") (pinfunction "GND_B_31") (pintype "passive"))
    )
    (net (code "69") (name "Net-(U3-GND_C)") (class "Default")
      (node (ref "R10") (pin "1") (pinfunction "1_1") (pintype "passive"))
      (node (ref "U3") (pin "23") (pinfunction "GND_C_23") (pintype "passive"))
    )
    (net (code "70") (name "Net-(U3-M3)") (class "Default")
      (node (ref "C13") (pin "2") (pinfunction "2_2") (pintype "passive"))
      (node (ref "U3") (pin "10") (pinfunction "VREG_10") (pintype "passive"))
      (node (ref "U3") (pin "11") (pinfunction "M3_11") (pintype "passive"))
    )
    (net (code "71") (name "Net-(U3-OC_ADJ)") (class "Default")
      (node (ref "R19") (pin "2") (pinfunction "2_2") (pintype "passive"))
      (node (ref "U3") (pin "7") (pinfunction "OC_ADJ_7") (pintype "passive"))
    )
    (net (code "72") (name "Net-(U4-AGND)") (class "Default")
      (node (ref "C12") (pin "1") (pinfunction "1_1") (pintype "passive"))
      (node (ref "R16") (pin "2") (pinfunction "2_2") (pintype "passive"))
      (node (ref "R18") (pin "1") (pinfunction "1_1") (pintype "passive"))
      (node (ref "U4") (pin "12") (pinfunction "M2_12") (pintype "passive"))
      (node (ref "U4") (pin "13") (pinfunction "M1_13") (pintype "passive"))
      (node (ref "U4") (pin "9") (pinfunction "AGND_9") (pintype "passive"))
    )
    (net (code "73") (name "Net-(U4-BST_A)") (class "Default")
      (node (ref "C17") (pin "2") (pinfunction "2_2") (pintype "passive"))
      (node (ref "U4") (pin "35") (pinfunction "BST_A_35") (pintype "passive"))
    )
    (net (code "74") (name "Net-(U4-BST_B)") (class "Default")
      (node (ref "C18") (pin "2") (pinfunction "2_2") (pintype "passive"))
      (node (ref "U4") (pin "28") (pinfunction "BST_B_28") (pintype "passive"))
    )
    (net (code "75") (name "Net-(U4-BST_C)") (class "Default")
      (node (ref "C19") (pin "2") (pinfunction "2_2") (pintype "passive"))
      (node (ref "U4") (pin "20") (pinfunction "BST_C_20") (pintype "passive"))
    )
    (net (code "76") (name "Net-(U4-GND_A)") (class "Default")
      (node (ref "R15") (pin "1") (pinfunction "1_1") (pintype "passive"))
      (node (ref "U4") (pin "32") (pinfunction "GND_A_32") (pintype "passive"))
    )
    (net (code "77") (name "Net-(U4-GND_B)") (class "Default")
      (node (ref "R14") (pin "1") (pinfunction "1_1") (pintype "passive"))
      (node (ref "U4") (pin "31") (pinfunction "GND_B_31") (pintype "passive"))
    )
    (net (code "78") (name "Net-(U4-GND_C)") (class "Default")
      (node (ref "R13") (pin "1") (pinfunction "1_1") (pintype "passive"))
      (node (ref "U4") (pin "23") (pinfunction "GND_C_23") (pintype "passive"))
    )
    (net (code "79") (name "Net-(U4-M3)") (class "Default")
      (node (ref "C12") (pin "2") (pinfunction "2_2") (pintype "passive"))
      (node (ref "U4") (pin "10") (pinfunction "VREG_10") (pintype "passive"))
      (node (ref "U4") (pin "11") (pinfunction "M3_11") (pintype "passive"))
    )
    (net (code "80") (name "Net-(U4-OC_ADJ)") (class "Default")
      (node (ref "R18") (pin "2") (pinfunction "2_2") (pintype "passive"))
      (node (ref "U4") (pin "7") (pinfunction "OC_ADJ_7") (pintype "passive"))
    )
    (net (code "81") (name "VCC") (class "Default")
      (node (ref "C10") (pin "2") (pinfunction "2_2") (pintype "passive"))
      (node (ref "C11") (pin "2") (pinfunction "2_2") (pintype "passive"))
      (node (ref "C3") (pin "1") (pinfunction "1_1") (pintype "passive"))
      (node (ref "C6") (pin "1") (pinfunction "+_1") (pintype "passive"))
      (node (ref "C8") (pin "1") (pinfunction "1_1") (pintype "passive"))
      (node (ref "C9") (pin "2") (pinfunction "2_2") (pintype "passive"))
      (node (ref "JP3") (pin "2") (pinfunction "2_2") (pintype "passive"))
      (node (ref "R1") (pin "1") (pinfunction "1_1") (pintype "passive"))
      (node (ref "R2") (pin "1") (pinfunction "1_1") (pintype "passive"))
      (node (ref "R6") (pin "1") (pinfunction "1_1") (pintype "passive"))
      (node (ref "SJ1") (pin "1") (pinfunction "1_1") (pintype "passive"))
      (node (ref "U$1") (pin "12") (pinfunction "VDD_2_12") (pintype "passive"))
      (node (ref "U$1") (pin "25") (pinfunction "AVDD_25") (pintype "passive"))
      (node (ref "U$1") (pin "32") (pinfunction "VDD_3_32") (pintype "passive"))
      (node (ref "U$1") (pin "48") (pinfunction "VDD_48") (pintype "passive"))
      (node (ref "U1") (pin "13") (pinfunction "VDD_13") (pintype "bidirectional"))
      (node (ref "U2") (pin "V_OUT") (pinfunction "V_OUT_V_OUT") (pintype "output"))
    )
    (net (code "82") (name "unconnected-(JP3-Pad6)") (class "Default")
      (node (ref "JP3") (pin "6") (pinfunction "6_6") (pintype "passive"))
    )
    (net (code "83") (name "unconnected-(U$1-*SS2{slash}FLT9{slash}T5CK{slash}CN11{slash}RG9-Pad10)") (class "Default")
      (node (ref "U$1") (pin "10") (pinfunction "*SS2/FLT9/T5CK/CN11/RG9_10") (pintype "passive"))
    )
    (net (code "84") (name "unconnected-(U$1-AN2{slash}CMP1C{slash}CMP2A{slash}*ASS1{slash}CN4{slash}RB2-Pad18)") (class "Default")
      (node (ref "U$1") (pin "18") (pinfunction "AN2/CMP1C/CMP2A/*ASS1/CN4/RB2_18") (pintype "passive"))
    )
    (net (code "85") (name "unconnected-(U$1-AN3{slash}CMP2B{slash}AINDX1{slash}CN5{slash}RB3-Pad17)") (class "Default")
      (node (ref "U$1") (pin "17") (pinfunction "AN3/CMP2B/AINDX1/CN5/RB3_17") (pintype "passive"))
    )
    (net (code "86") (name "unconnected-(U$1-AN4{slash}CMP2C{slash}CMP3A{slash}AQEA1{slash}CN6{slash}RB4-Pad16)") (class "Default")
      (node (ref "U$1") (pin "16") (pinfunction "AN4/CMP2C/CMP3A/AQEA1/CN6/RB4_16") (pintype "passive"))
    )
    (net (code "87") (name "unconnected-(U$1-AN5{slash}CMP3B{slash}AQEB1{slash}CN7{slash}RB5-Pad15)") (class "Default")
      (node (ref "U$1") (pin "15") (pinfunction "AN5/CMP3B/AQEB1/CN7/RB5_15") (pintype "passive"))
    )
    (net (code "88") (name "unconnected-(U$1-AN8{slash}*U2CTS{slash}RB8-Pad27)") (class "Default")
      (node (ref "U$1") (pin "27") (pinfunction "AN8/*U2CTS/RB8_27") (pintype "passive"))
    )
    (net (code "89") (name "unconnected-(U$1-AN9{slash}DACOUT{slash}RB9-Pad28)") (class "Default")
      (node (ref "U$1") (pin "28") (pinfunction "AN9/DACOUT/RB9_28") (pintype "passive"))
    )
    (net (code "90") (name "unconnected-(U$1-AN10{slash}RB10-Pad29)") (class "Default")
      (node (ref "U$1") (pin "29") (pinfunction "AN10/RB10_29") (pintype "passive"))
    )
    (net (code "91") (name "unconnected-(U$1-AN11{slash}EXTREF{slash}RB11-Pad30)") (class "Default")
      (node (ref "U$1") (pin "30") (pinfunction "AN11/EXTREF/RB11_30") (pintype "passive"))
    )
    (net (code "92") (name "unconnected-(U$1-AN16{slash}T2CK{slash}RC1-Pad4)") (class "Default")
      (node (ref "U$1") (pin "4") (pinfunction "AN16/T2CK/RC1_4") (pintype "passive"))
    )
    (net (code "93") (name "unconnected-(U$1-AN17{slash}T3CK{slash}RC2-Pad5)") (class "Default")
      (node (ref "U$1") (pin "5") (pinfunction "AN17/T3CK/RC2_5") (pintype "passive"))
    )
    (net (code "94") (name "unconnected-(U$1-OSC1{slash}CLKIN{slash}RC12-Pad49)") (class "Default")
      (node (ref "U$1") (pin "49") (pinfunction "OSC1/CLKIN/RC12_49") (pintype "passive"))
    )
    (net (code "95") (name "unconnected-(U$1-OSC2{slash}REFCLKO{slash}CLKO{slash}RC15-Pad50)") (class "Default")
      (node (ref "U$1") (pin "50") (pinfunction "OSC2/REFCLKO/CLKO/RC15_50") (pintype "passive"))
    )
    (net (code "96") (name "unconnected-(U$1-PGEC3{slash}AN1{slash}CMP1B{slash}CN3{slash}RB1-Pad19)") (class "Default")
      (node (ref "U$1") (pin "19") (pinfunction "PGEC3/AN1/CMP1B/CN3/RB1_19") (pintype "passive"))
    )
    (net (code "97") (name "unconnected-(U$1-PGED3{slash}AN0{slash}CMP1A{slash}CMP4C{slash}CN2{slash}RB0-Pad20)") (class "Default")
      (node (ref "U$1") (pin "20") (pinfunction "PGED3/AN0/CMP1A/CMP4C/CN2/RB0_20") (pintype "passive"))
    )
    (net (code "98") (name "unconnected-(U$1-PWM1L1{slash}FLT8{slash}RE0-Pad76)") (class "Default")
      (node (ref "U$1") (pin "76") (pinfunction "PWM1L1/FLT8/RE0_76") (pintype "passive"))
    )
    (net (code "99") (name "unconnected-(U$1-PWM2L{slash}RE2-Pad78)") (class "Default")
      (node (ref "U$1") (pin "78") (pinfunction "PWM2L/RE2_78") (pintype "passive"))
    )
    (net (code "100") (name "unconnected-(U$1-PWM3L{slash}RE4-Pad80)") (class "Default")
      (node (ref "U$1") (pin "80") (pinfunction "PWM3L/RE4_80") (pintype "passive"))
    )
    (net (code "101") (name "unconnected-(U$1-PWM4L{slash}RE6-Pad2)") (class "Default")
      (node (ref "U$1") (pin "2") (pinfunction "PWM4L/RE6_2") (pintype "passive"))
    )
    (net (code "102") (name "unconnected-(U$1-PWM5L{slash}CN15{slash}RD6-Pad68)") (class "Default")
      (node (ref "U$1") (pin "68") (pinfunction "PWM5L/CN15/RD6_68") (pintype "passive"))
    )
    (net (code "103") (name "unconnected-(U$1-PWM6L{slash}CN13{slash}RD4-Pad66)") (class "Default")
      (node (ref "U$1") (pin "66") (pinfunction "PWM6L/CN13/RD4_66") (pintype "passive"))
    )
    (net (code "104") (name "unconnected-(U$1-PWM7H{slash}OC4{slash}SYNCO1{slash}RD3-Pad63)") (class "Default")
      (node (ref "U$1") (pin "63") (pinfunction "PWM7H/OC4/SYNCO1/RD3_63") (pintype "passive"))
    )
    (net (code "105") (name "unconnected-(U$1-PWM7L{slash}CN19{slash}RD13-Pad65)") (class "Default")
      (node (ref "U$1") (pin "65") (pinfunction "PWM7L/CN19/RD13_65") (pintype "passive"))
    )
    (net (code "106") (name "unconnected-(U$1-PWM8H{slash}RA10-Pad24)") (class "Default")
      (node (ref "U$1") (pin "24") (pinfunction "PWM8H/RA10_24") (pintype "passive"))
    )
    (net (code "107") (name "unconnected-(U$1-PWM8L{slash}RA9-Pad23)") (class "Default")
      (node (ref "U$1") (pin "23") (pinfunction "PWM8L/RA9_23") (pintype "passive"))
    )
    (net (code "108") (name "unconnected-(U$1-SCK1{slash}INT0{slash}RF6-Pad45)") (class "Default")
      (node (ref "U$1") (pin "45") (pinfunction "SCK1/INT0/RF6_45") (pintype "passive"))
    )
    (net (code "109") (name "unconnected-(U$1-SCK2{slash}FLT12{slash}CN8{slash}RG6-Pad6)") (class "Default")
      (node (ref "U$1") (pin "6") (pinfunction "SCK2/FLT12/CN8/RG6_6") (pintype "passive"))
    )
    (net (code "110") (name "unconnected-(U$1-SCL2{slash}INT3{slash}FLT20{slash}RA14-Pad52)") (class "Default")
      (node (ref "U$1") (pin "52") (pinfunction "SCL2/INT3/FLT20/RA14_52") (pintype "passive"))
    )
    (net (code "111") (name "unconnected-(U$1-SDA2{slash}INT4{slash}FLT19{slash}RA15-Pad53)") (class "Default")
      (node (ref "U$1") (pin "53") (pinfunction "SDA2/INT4/FLT19/RA15_53") (pintype "passive"))
    )
    (net (code "112") (name "unconnected-(U$1-SDI1{slash}RF7-Pad44)") (class "Default")
      (node (ref "U$1") (pin "44") (pinfunction "SDI1/RF7_44") (pintype "passive"))
    )
    (net (code "113") (name "unconnected-(U$1-SDI2{slash}FLT11{slash}CN9{slash}RG7-Pad7)") (class "Default")
      (node (ref "U$1") (pin "7") (pinfunction "SDI2/FLT11/CN9/RG7_7") (pintype "passive"))
    )
    (net (code "114") (name "unconnected-(U$1-SDO1{slash}RF8-Pad43)") (class "Default")
      (node (ref "U$1") (pin "43") (pinfunction "SDO1/RF8_43") (pintype "passive"))
    )
    (net (code "115") (name "unconnected-(U$1-SDO2{slash}FLT10{slash}CN10{slash}RG8-Pad8)") (class "Default")
      (node (ref "U$1") (pin "8") (pinfunction "SDO2/FLT10/CN10/RG8_8") (pintype "passive"))
    )
    (net (code "116") (name "unconnected-(U$1-TDO{slash}FLT14{slash}INT2{slash}RE9-Pad14)") (class "Default")
      (node (ref "U$1") (pin "14") (pinfunction "TDO/FLT14/INT2/RE9_14") (pintype "passive"))
    )
    (net (code "117") (name "unconnected-(U$1-TMS{slash}FLT13{slash}INT1{slash}RE8-Pad13)") (class "Default")
      (node (ref "U$1") (pin "13") (pinfunction "TMS/FLT13/INT1/RE8_13") (pintype "passive"))
    )
    (net (code "118") (name "unconnected-(U2-PadINHIBIT)") (class "Default")
      (node (ref "U2") (pin "INHIBIT") (pinfunction "INHIBIT_INHIBIT") (pintype "input"))
    )
    (net (code "119") (name "unconnected-(U3-NC-Pad27)") (class "Default")
      (node (ref "U3") (pin "27") (pinfunction "NC_27") (pintype "passive"))
    )
    (net (code "120") (name "unconnected-(U3-NC_2-Pad26)") (class "Default")
      (node (ref "U3") (pin "26") (pinfunction "NC_2_26") (pintype "passive"))
    )
    (net (code "121") (name "unconnected-(U4-NC-Pad27)") (class "Default")
      (node (ref "U4") (pin "27") (pinfunction "NC_27") (pintype "passive"))
    )
    (net (code "122") (name "unconnected-(U4-NC_2-Pad26)") (class "Default")
      (node (ref "U4") (pin "26") (pinfunction "NC_2_26") (pintype "passive"))
    )
  )
)
